# Fri3d_2020_Time_Blaster_00.net
KiCad netlist of a schematic drawn in Altium Designer
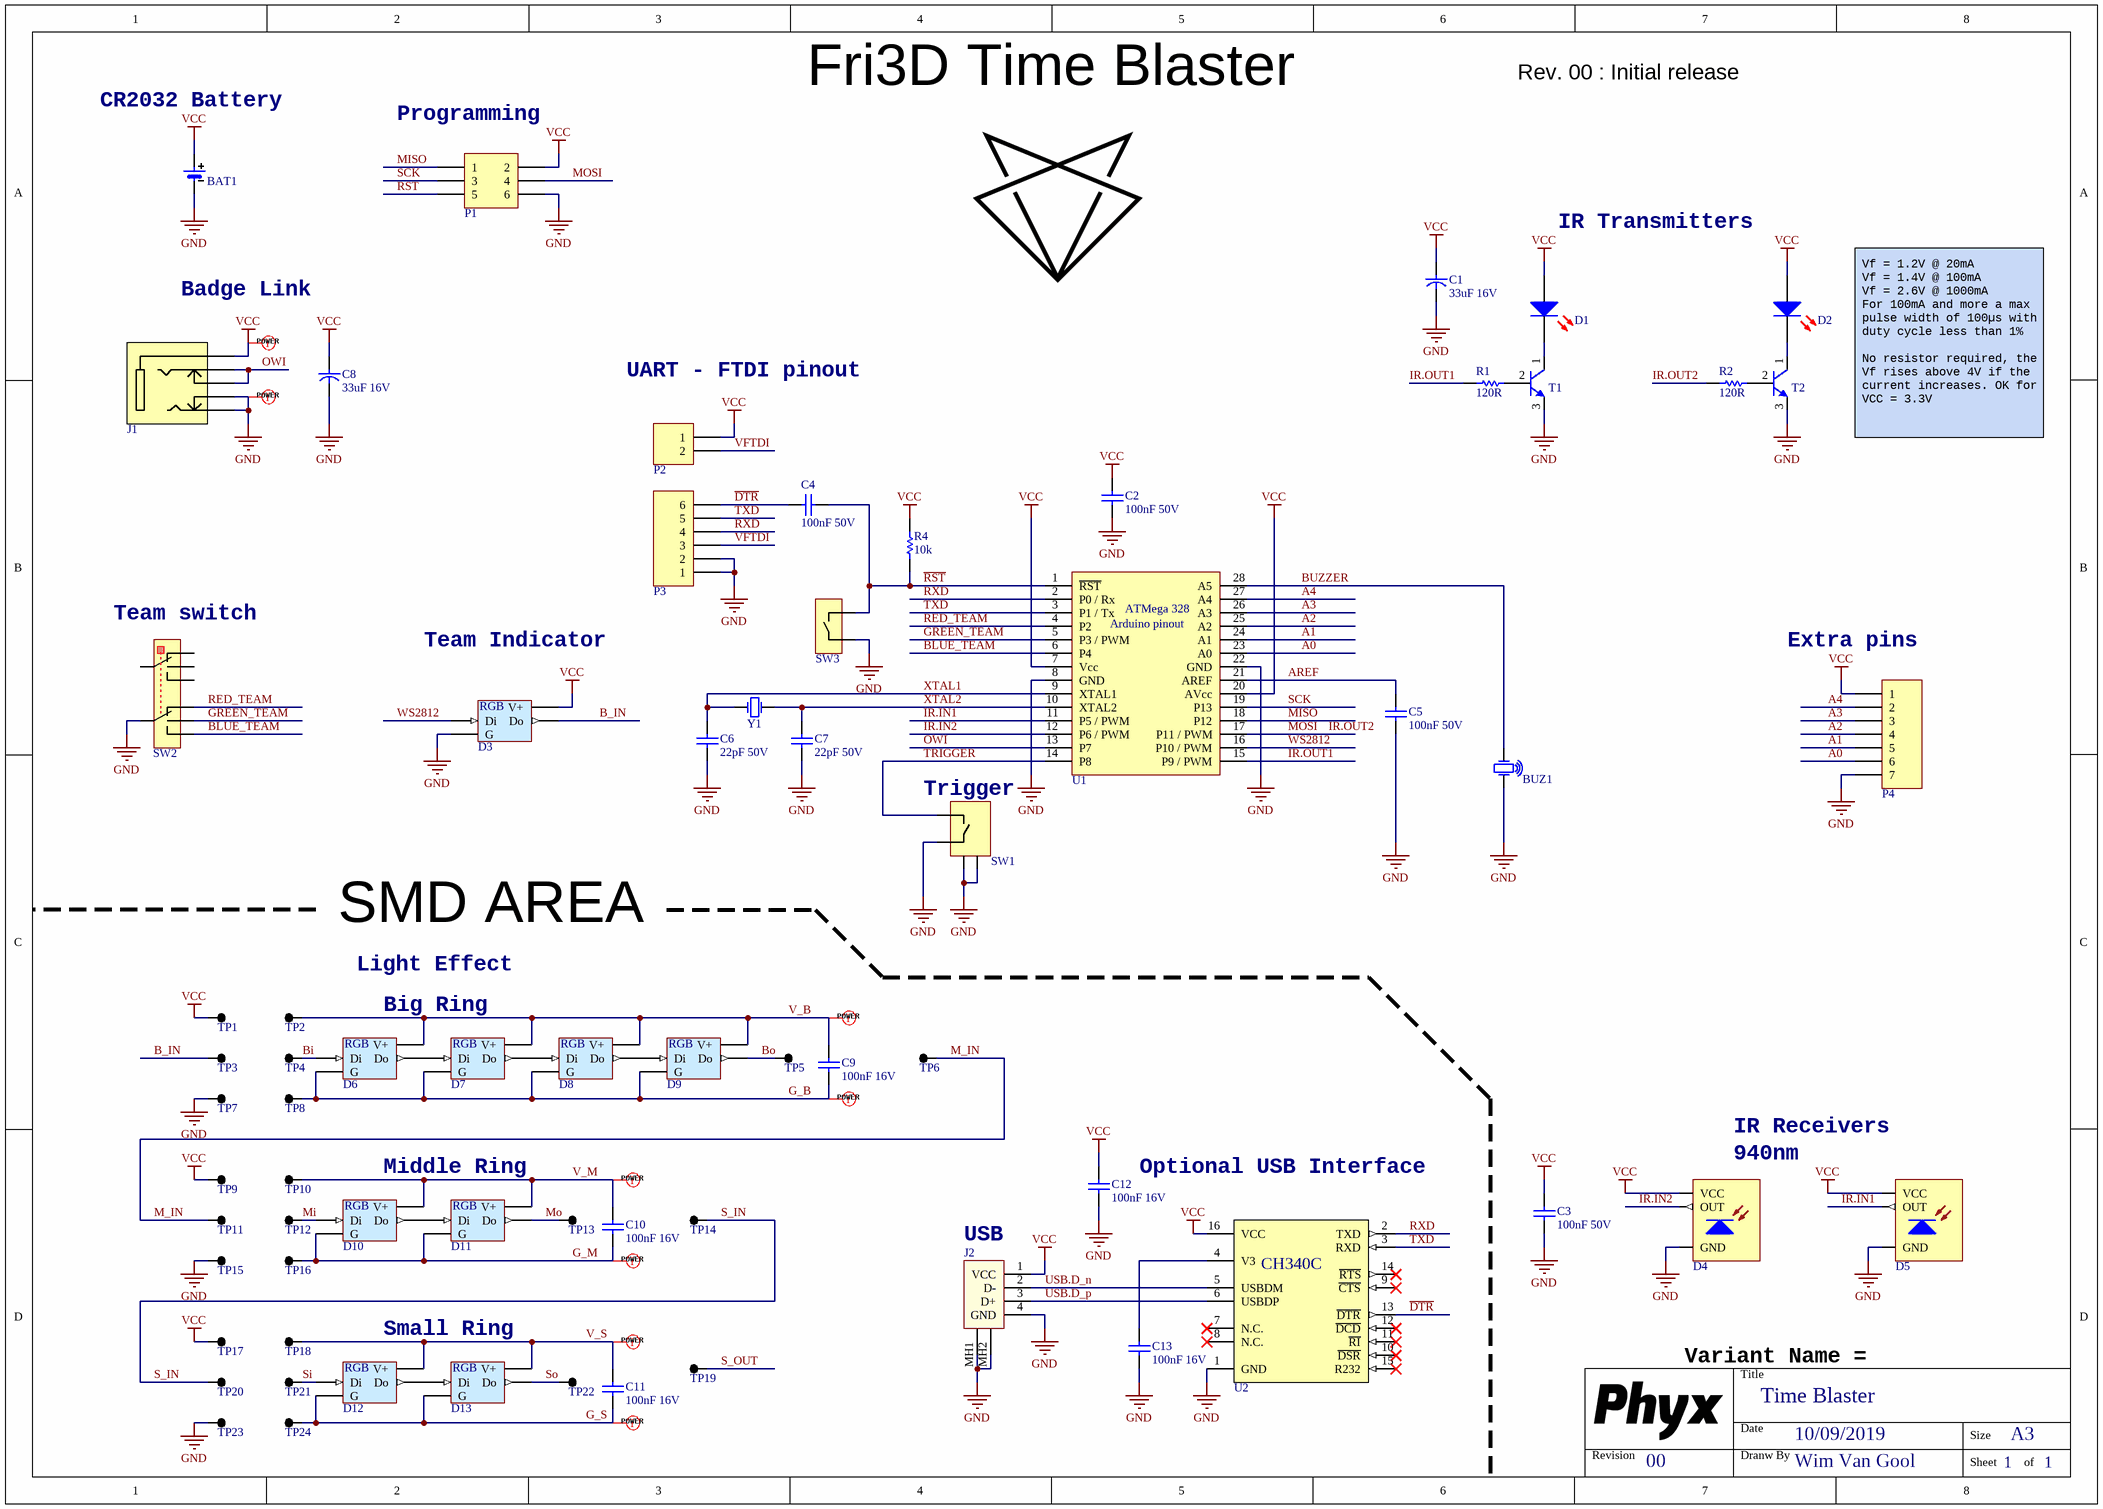
[diagram p0: Fri3d_2020_Time_Blaster_00.SchDoc]

(export (version "E")
  (design (tool "Eeschema 10.0.6"))
  (components
    (comp (ref "BAT1")
      (value "CR2032 Battery Holder")
      (footprint "BAT_CR2032_China")
      (description "=Description")
      (libsource (lib "Phyx_Components") (part "BAT_2"))
    )
    (comp (ref "BUZ1")
      (value "14x14x7mm Piezo Buzzer Transducer 80dB")
      (footprint "CUI_CEP-1162")
      (description "Crystal Oscillator")
      (libsource (lib "Phyx_Components") (part "Buzzer"))
    )
    (comp (ref "C1")
      (value "33uF 16V")
      (footprint "C_4x7_1.5mm")
      (description "Capacitor electrolyt")
      (fields (field (name "Comment") "CAP_POL"))
      (libsource (lib "Phyx_Components") (part "CAP_POL"))
    )
    (comp (ref "C2")
      (value "100nF 50V")
      (footprint "C_5.08mm")
      (description "Capacitor Ceramic")
      (fields (field (name "Comment") "CAP_CERAMIC"))
      (libsource (lib "Phyx_Components") (part "CAP_CERAMIC"))
    )
    (comp (ref "C3")
      (value "100nF 50V")
      (footprint "C_5.08mm")
      (description "Capacitor Ceramic")
      (fields (field (name "Comment") "CAP_CERAMIC"))
      (libsource (lib "Phyx_Components") (part "CAP_CERAMIC"))
    )
    (comp (ref "C4")
      (value "100nF 50V")
      (footprint "C_5.08mm")
      (description "Capacitor Ceramic")
      (fields (field (name "Comment") "CAP_CERAMIC"))
      (libsource (lib "Phyx_Components") (part "CAP_CERAMIC"))
    )
    (comp (ref "C5")
      (value "100nF 50V")
      (footprint "C_5.08mm")
      (description "Capacitor Ceramic")
      (fields (field (name "Comment") "CAP_CERAMIC"))
      (libsource (lib "Phyx_Components") (part "CAP_CERAMIC"))
    )
    (comp (ref "C6")
      (value "22pF 50V")
      (footprint "C_5.08mm")
      (description "Capacitor Ceramic")
      (fields (field (name "Comment") "CAP_CERAMIC"))
      (libsource (lib "Phyx_Components") (part "CAP_CERAMIC"))
    )
    (comp (ref "C7")
      (value "22pF 50V")
      (footprint "C_5.08mm")
      (description "Capacitor Ceramic")
      (fields (field (name "Comment") "CAP_CERAMIC"))
      (libsource (lib "Phyx_Components") (part "CAP_CERAMIC"))
    )
    (comp (ref "C8")
      (value "33uF 16V")
      (footprint "C_4x7_1.5mm")
      (description "Capacitor electrolyt")
      (fields (field (name "Comment") "CAP_POL"))
      (libsource (lib "Phyx_Components") (part "CAP_POL"))
    )
    (comp (ref "C9")
      (value "100nF 16V")
      (footprint "C0805_N")
      (description "Capacitor Ceramic")
      (fields (field (name "Comment") "CAP_CERAMIC"))
      (libsource (lib "Phyx_Components") (part "CAP_CERAMIC"))
    )
    (comp (ref "C10")
      (value "100nF 16V")
      (footprint "C0805_N")
      (description "Capacitor Ceramic")
      (fields (field (name "Comment") "CAP_CERAMIC"))
      (libsource (lib "Phyx_Components") (part "CAP_CERAMIC"))
    )
    (comp (ref "C11")
      (value "100nF 16V")
      (footprint "C0805_N")
      (description "Capacitor Ceramic")
      (fields (field (name "Comment") "CAP_CERAMIC"))
      (libsource (lib "Phyx_Components") (part "CAP_CERAMIC"))
    )
    (comp (ref "C12")
      (value "100nF 16V")
      (footprint "C0805_N")
      (description "Capacitor Ceramic")
      (fields (field (name "Comment") "CAP_CERAMIC"))
      (libsource (lib "Phyx_Components") (part "CAP_CERAMIC"))
    )
    (comp (ref "C13")
      (value "100nF 16V")
      (footprint "C0805_N")
      (description "Capacitor Ceramic")
      (fields (field (name "Comment") "CAP_CERAMIC"))
      (libsource (lib "Phyx_Components") (part "CAP_CERAMIC"))
    )
    (comp (ref "D1")
      (value "5mm IR LED, 940nm, 100mA, 1.35V, 25Deg")
      (footprint "LED_5MM_RD")
      (description "=Description")
      (libsource (lib "Phyx_Components") (part "LED_RED"))
    )
    (comp (ref "D2")
      (value "5mm IR LED, 940nm, 100mA, 1.35V, 25Deg")
      (footprint "LED_5MM_RD")
      (description "=Description")
      (libsource (lib "Phyx_Components") (part "LED_RED"))
    )
    (comp (ref "D3")
      (value "WS2812 based digital RGB LED 5mm")
      (footprint "LED_5mm_RGB")
      (description "=Description")
      (libsource (lib "Phyx_Components") (part "LED_RGB_WS2812B_5mm"))
    )
    (comp (ref "D4")
      (value "IRM-3638N3F14 Infrared Receiver 38 kHz 45° 2.7-5.5V")
      (footprint "VIS_TSOP381x_BENT")
      (description "=Description")
      (libsource (lib "Phyx_Components") (part "PHO_IR_TSOP381x"))
    )
    (comp (ref "D5")
      (value "IRM-3638N3F14 Infrared Receiver 38 kHz 45° 2.7-5.5V")
      (footprint "VIS_TSOP381x_BENT")
      (description "=Description")
      (libsource (lib "Phyx_Components") (part "PHO_IR_TSOP381x"))
    )
    (comp (ref "D6")
      (value "WS2812 based digital RGB LED 5050 Black package")
      (footprint "LED_5050_WS2812B_BLACK")
      (description "=Description")
      (libsource (lib "Phyx_Components") (part "LED_RGB_WS2812B_5050"))
    )
    (comp (ref "D7")
      (value "WS2812 based digital RGB LED 5050 Black package")
      (footprint "LED_5050_WS2812B_BLACK")
      (description "=Description")
      (libsource (lib "Phyx_Components") (part "LED_RGB_WS2812B_5050"))
    )
    (comp (ref "D8")
      (value "WS2812 based digital RGB LED 5050 Black package")
      (footprint "LED_5050_WS2812B_BLACK")
      (description "=Description")
      (libsource (lib "Phyx_Components") (part "LED_RGB_WS2812B_5050"))
    )
    (comp (ref "D9")
      (value "WS2812 based digital RGB LED 5050 Black package")
      (footprint "LED_5050_WS2812B_BLACK")
      (description "=Description")
      (libsource (lib "Phyx_Components") (part "LED_RGB_WS2812B_5050"))
    )
    (comp (ref "D10")
      (value "WS2812 based digital RGB LED 5050 Black package")
      (footprint "LED_5050_WS2812B_BLACK")
      (description "=Description")
      (libsource (lib "Phyx_Components") (part "LED_RGB_WS2812B_5050"))
    )
    (comp (ref "D11")
      (value "WS2812 based digital RGB LED 5050 Black package")
      (footprint "LED_5050_WS2812B_BLACK")
      (description "=Description")
      (libsource (lib "Phyx_Components") (part "LED_RGB_WS2812B_5050"))
    )
    (comp (ref "D12")
      (value "WS2812 based digital RGB LED 5050 Black package")
      (footprint "LED_5050_WS2812B_BLACK")
      (description "=Description")
      (libsource (lib "Phyx_Components") (part "LED_RGB_WS2812B_5050"))
    )
    (comp (ref "D13")
      (value "WS2812 based digital RGB LED 5050 Black package")
      (footprint "LED_5050_WS2812B_BLACK")
      (description "=Description")
      (libsource (lib "Phyx_Components") (part "LED_RGB_WS2812B_5050"))
    )
    (comp (ref "J1")
      (value "3.5mm jack, dual switch, black, 3 contacts")
      (footprint "CUI_SJ1-3525NG")
      (description "=Description")
      (libsource (lib "Phyx_Components") (part "CUI_SJ1-3525NG"))
    )
    (comp (ref "J2")
      (value "Vertical USB B 61400416121")
      (footprint "WE_61400416121")
      (libsource (lib "Phyx_Components") (part "USB_A"))
    )
    (comp (ref "P1")
      (value "Boxed Header 3X2")
      (footprint "B_HDR2X3")
      (libsource (lib "Phyx_Components") (part "Header 3X2"))
    )
    (comp (ref "P2")
      (value "Easy to solder connection")
      (footprint "SOLDER_SW_V_1MM")
      (libsource (lib "Phyx_Components") (part "Header 2"))
    )
    (comp (ref "P3")
      (value "Header 6")
      (footprint "HDR1X6")
      (libsource (lib "Phyx_Components") (part "Header 6"))
    )
    (comp (ref "P4")
      (value "Header 7")
      (footprint "HDR1X7")
      (libsource (lib "Phyx_Components") (part "Header 7"))
    )
    (comp (ref "R1")
      (value "120R")
      (footprint "RES_10mm")
      (fields (field (name "Comment") "RESISTOR"))
      (libsource (lib "Phyx_Components") (part "RESISTOR"))
    )
    (comp (ref "R2")
      (value "120R")
      (footprint "RES_10mm")
      (fields (field (name "Comment") "RESISTOR"))
      (libsource (lib "Phyx_Components") (part "RESISTOR"))
    )
    (comp (ref "R4")
      (value "10k")
      (footprint "RES_10mm")
      (fields (field (name "Comment") "RESISTOR"))
      (libsource (lib "Phyx_Components") (part "RESISTOR"))
    )
    (comp (ref "SW1")
      (value "Tact switch, RA, 3,85mm")
      (footprint "TACTSW_RA_385")
      (libsource (lib "Phyx_Components") (part "SW_TACT_RA"))
    )
    (comp (ref "SW2")
      (value "Slide switch dual pole triple throw")
      (footprint "CK_JS203011CQN")
      (libsource (lib "Phyx_Components") (part "SW_2P3T"))
    )
    (comp (ref "SW3")
      (value "Default TH TACT")
      (footprint "TACTSW")
      (libsource (lib "Phyx_Components") (part "SW_TACT"))
    )
    (comp (ref "T1")
      (value "0.2A 40V 100hfe NPN Transistor")
      (footprint "TO-92A")
      (libsource (lib "Phyx_Components") (part "NPN_EBC"))
    )
    (comp (ref "T2")
      (value "0.2A 40V 100hfe NPN Transistor")
      (footprint "TO-92A")
      (libsource (lib "Phyx_Components") (part "NPN_EBC"))
    )
    (comp (ref "TP1")
      (value "TEST_PAD")
      (footprint "TP_2x3mm")
      (libsource (lib "Phyx_Components") (part "TEST_PAD"))
    )
    (comp (ref "TP2")
      (value "TEST_PAD")
      (footprint "TP_2x3mm")
      (libsource (lib "Phyx_Components") (part "TEST_PAD"))
    )
    (comp (ref "TP3")
      (value "TEST_PAD")
      (footprint "TP_2x3mm")
      (libsource (lib "Phyx_Components") (part "TEST_PAD"))
    )
    (comp (ref "TP4")
      (value "TEST_PAD")
      (footprint "TP_2x3mm")
      (libsource (lib "Phyx_Components") (part "TEST_PAD"))
    )
    (comp (ref "TP5")
      (value "TEST_PAD")
      (footprint "TP_2x3mm")
      (libsource (lib "Phyx_Components") (part "TEST_PAD"))
    )
    (comp (ref "TP6")
      (value "TEST_PAD")
      (footprint "TP_2x3mm")
      (libsource (lib "Phyx_Components") (part "TEST_PAD"))
    )
    (comp (ref "TP7")
      (value "TEST_PAD")
      (footprint "TP_2x3mm")
      (libsource (lib "Phyx_Components") (part "TEST_PAD"))
    )
    (comp (ref "TP8")
      (value "TEST_PAD")
      (footprint "TP_2x3mm")
      (libsource (lib "Phyx_Components") (part "TEST_PAD"))
    )
    (comp (ref "TP9")
      (value "TEST_PAD")
      (footprint "TP_2x3mm")
      (libsource (lib "Phyx_Components") (part "TEST_PAD"))
    )
    (comp (ref "TP10")
      (value "TEST_PAD")
      (footprint "TP_2x3mm")
      (libsource (lib "Phyx_Components") (part "TEST_PAD"))
    )
    (comp (ref "TP11")
      (value "TEST_PAD")
      (footprint "TP_2x3mm")
      (libsource (lib "Phyx_Components") (part "TEST_PAD"))
    )
    (comp (ref "TP12")
      (value "TEST_PAD")
      (footprint "TP_2x3mm")
      (libsource (lib "Phyx_Components") (part "TEST_PAD"))
    )
    (comp (ref "TP13")
      (value "TEST_PAD")
      (footprint "TP_2x3mm")
      (libsource (lib "Phyx_Components") (part "TEST_PAD"))
    )
    (comp (ref "TP14")
      (value "TEST_PAD")
      (footprint "TP_2x3mm")
      (libsource (lib "Phyx_Components") (part "TEST_PAD"))
    )
    (comp (ref "TP15")
      (value "TEST_PAD")
      (footprint "TP_2x3mm")
      (libsource (lib "Phyx_Components") (part "TEST_PAD"))
    )
    (comp (ref "TP16")
      (value "TEST_PAD")
      (footprint "TP_2x3mm")
      (libsource (lib "Phyx_Components") (part "TEST_PAD"))
    )
    (comp (ref "TP17")
      (value "TEST_PAD")
      (footprint "TP_2x3mm")
      (libsource (lib "Phyx_Components") (part "TEST_PAD"))
    )
    (comp (ref "TP18")
      (value "TEST_PAD")
      (footprint "TP_2x3mm")
      (libsource (lib "Phyx_Components") (part "TEST_PAD"))
    )
    (comp (ref "TP19")
      (value "TEST_PAD")
      (footprint "TP_2x3mm")
      (libsource (lib "Phyx_Components") (part "TEST_PAD"))
    )
    (comp (ref "TP20")
      (value "TEST_PAD")
      (footprint "TP_2x3mm")
      (libsource (lib "Phyx_Components") (part "TEST_PAD"))
    )
    (comp (ref "TP21")
      (value "TEST_PAD")
      (footprint "TP_2x3mm")
      (libsource (lib "Phyx_Components") (part "TEST_PAD"))
    )
    (comp (ref "TP22")
      (value "TEST_PAD")
      (footprint "TP_2x3mm")
      (libsource (lib "Phyx_Components") (part "TEST_PAD"))
    )
    (comp (ref "TP23")
      (value "TEST_PAD")
      (footprint "TP_2x3mm")
      (libsource (lib "Phyx_Components") (part "TEST_PAD"))
    )
    (comp (ref "TP24")
      (value "TEST_PAD")
      (footprint "TP_2x3mm")
      (libsource (lib "Phyx_Components") (part "TEST_PAD"))
    )
    (comp (ref "U1")
      (value "8-bit MCU")
      (footprint "DIP_N_28")
      (libsource (lib "Phyx_Components") (part "ATMega328_DIP28"))
    )
    (comp (ref "U2")
      (value "USB to full UART with internal crystal")
      (footprint "SOIC_N_16")
      (description "=Description")
      (libsource (lib "Phyx_Components") (part "CH340C"))
    )
    (comp (ref "Y1")
      (value "16MHz 18pF HC49US")
      (footprint "HC49US")
      (description "Crystal Oscillator")
      (libsource (lib "Phyx_Components") (part "XTAL"))
    )
  )
  (nets
    (net (code "1") (name "/A0") (class "Default")
      (node (ref "P4") (pin "6") (pinfunction "6_6") (pintype "passive"))
      (node (ref "U1") (pin "23") (pinfunction "A0_23") (pintype "passive"))
    )
    (net (code "2") (name "/A1") (class "Default")
      (node (ref "P4") (pin "5") (pinfunction "5_5") (pintype "passive"))
      (node (ref "U1") (pin "24") (pinfunction "A1_24") (pintype "passive"))
    )
    (net (code "3") (name "/A2") (class "Default")
      (node (ref "P4") (pin "4") (pinfunction "4_4") (pintype "passive"))
      (node (ref "U1") (pin "25") (pinfunction "A2_25") (pintype "passive"))
    )
    (net (code "4") (name "/A3") (class "Default")
      (node (ref "P4") (pin "3") (pinfunction "3_3") (pintype "passive"))
      (node (ref "U1") (pin "26") (pinfunction "A3_26") (pintype "passive"))
    )
    (net (code "5") (name "/A4") (class "Default")
      (node (ref "P4") (pin "2") (pinfunction "2_2") (pintype "passive"))
      (node (ref "U1") (pin "27") (pinfunction "A4_27") (pintype "passive"))
    )
    (net (code "6") (name "/AREF") (class "Default")
      (node (ref "C5") (pin "1") (pinfunction "1_1") (pintype "passive"))
      (node (ref "U1") (pin "21") (pinfunction "AREF_21") (pintype "passive"))
    )
    (net (code "7") (name "/BLUE_TEAM") (class "Default")
      (node (ref "SW2") (pin "8") (pinfunction "8_8") (pintype "passive"))
      (node (ref "U1") (pin "6") (pinfunction "P4_6") (pintype "passive"))
    )
    (net (code "8") (name "/BUZZER") (class "Default")
      (node (ref "BUZ1") (pin "1") (pinfunction "OSC1_1") (pintype "passive"))
      (node (ref "U1") (pin "28") (pinfunction "A5_28") (pintype "passive"))
    )
    (net (code "9") (name "/B_IN") (class "Default")
      (node (ref "D3") (pin "1") (pinfunction "Do_1") (pintype "output"))
      (node (ref "TP3") (pin "1") (pinfunction "1_1") (pintype "passive"))
    )
    (net (code "10") (name "/Bi") (class "Default")
      (node (ref "D6") (pin "4") (pinfunction "Di_4") (pintype "input"))
      (node (ref "TP4") (pin "1") (pinfunction "1_1") (pintype "passive"))
    )
    (net (code "11") (name "/Bo") (class "Default")
      (node (ref "D9") (pin "2") (pinfunction "Do_2") (pintype "output"))
      (node (ref "TP5") (pin "1") (pinfunction "1_1") (pintype "passive"))
    )
    (net (code "12") (name "/GREEN_TEAM") (class "Default")
      (node (ref "SW2") (pin "6") (pinfunction "6_6") (pintype "passive"))
      (node (ref "U1") (pin "5") (pinfunction "P3_/_PWM_5") (pintype "passive"))
    )
    (net (code "13") (name "/G_B") (class "Default")
      (node (ref "C9") (pin "2") (pinfunction "2_2") (pintype "passive"))
      (node (ref "D6") (pin "3") (pinfunction "G_3") (pintype "power_in"))
      (node (ref "D7") (pin "3") (pinfunction "G_3") (pintype "power_in"))
      (node (ref "D8") (pin "3") (pinfunction "G_3") (pintype "power_in"))
      (node (ref "D9") (pin "3") (pinfunction "G_3") (pintype "power_in"))
      (node (ref "TP8") (pin "1") (pinfunction "1_1") (pintype "passive"))
    )
    (net (code "14") (name "/G_M") (class "Default")
      (node (ref "C10") (pin "2") (pinfunction "2_2") (pintype "passive"))
      (node (ref "D10") (pin "3") (pinfunction "G_3") (pintype "power_in"))
      (node (ref "D11") (pin "3") (pinfunction "G_3") (pintype "power_in"))
      (node (ref "TP16") (pin "1") (pinfunction "1_1") (pintype "passive"))
    )
    (net (code "15") (name "/G_S") (class "Default")
      (node (ref "C11") (pin "2") (pinfunction "2_2") (pintype "passive"))
      (node (ref "D12") (pin "3") (pinfunction "G_3") (pintype "power_in"))
      (node (ref "D13") (pin "3") (pinfunction "G_3") (pintype "power_in"))
      (node (ref "TP24") (pin "1") (pinfunction "1_1") (pintype "passive"))
    )
    (net (code "16") (name "/IR.IN1") (class "Default")
      (node (ref "D5") (pin "1") (pinfunction "OUT_1") (pintype "output"))
      (node (ref "U1") (pin "11") (pinfunction "P5_/_PWM_11") (pintype "passive"))
    )
    (net (code "17") (name "/IR.IN2") (class "Default")
      (node (ref "D4") (pin "1") (pinfunction "OUT_1") (pintype "output"))
      (node (ref "U1") (pin "12") (pinfunction "P6_/_PWM_12") (pintype "passive"))
    )
    (net (code "18") (name "/IR.OUT1") (class "Default")
      (node (ref "R1") (pin "2") (pinfunction "2_2") (pintype "passive"))
      (node (ref "U1") (pin "15") (pinfunction "P9_/_PWM_15") (pintype "passive"))
    )
    (net (code "19") (name "/IR.OUT2") (class "Default")
      (node (ref "P1") (pin "4") (pinfunction "4_4") (pintype "passive"))
      (node (ref "R2") (pin "2") (pinfunction "2_2") (pintype "passive"))
      (node (ref "U1") (pin "17") (pinfunction "P11_/_PWM_17") (pintype "passive"))
    )
    (net (code "20") (name "/MISO") (class "Default")
      (node (ref "P1") (pin "1") (pinfunction "1_1") (pintype "passive"))
      (node (ref "U1") (pin "18") (pinfunction "P12_18") (pintype "passive"))
    )
    (net (code "21") (name "/M_IN") (class "Default")
      (node (ref "TP11") (pin "1") (pinfunction "1_1") (pintype "passive"))
      (node (ref "TP6") (pin "1") (pinfunction "1_1") (pintype "passive"))
    )
    (net (code "22") (name "/Mi") (class "Default")
      (node (ref "D10") (pin "4") (pinfunction "Di_4") (pintype "input"))
      (node (ref "TP12") (pin "1") (pinfunction "1_1") (pintype "passive"))
    )
    (net (code "23") (name "/Mo") (class "Default")
      (node (ref "D11") (pin "2") (pinfunction "Do_2") (pintype "output"))
      (node (ref "TP13") (pin "1") (pinfunction "1_1") (pintype "passive"))
    )
    (net (code "24") (name "/OWI") (class "Default")
      (node (ref "J1") (pin "3") (pinfunction "Ring_3") (pintype "passive"))
      (node (ref "J1") (pin "5") (pinfunction "5_5") (pintype "passive"))
      (node (ref "U1") (pin "13") (pinfunction "P7_13") (pintype "passive"))
    )
    (net (code "25") (name "/RED_TEAM") (class "Default")
      (node (ref "SW2") (pin "5") (pinfunction "5_5") (pintype "passive"))
      (node (ref "U1") (pin "4") (pinfunction "P2_4") (pintype "passive"))
    )
    (net (code "26") (name "/RXD") (class "Default")
      (node (ref "P3") (pin "4") (pinfunction "4_4") (pintype "passive"))
      (node (ref "U1") (pin "2") (pinfunction "P0_/_Rx_2") (pintype "passive"))
      (node (ref "U2") (pin "2") (pinfunction "TXD_2") (pintype "output"))
    )
    (net (code "27") (name "/SCK") (class "Default")
      (node (ref "P1") (pin "3") (pinfunction "3_3") (pintype "passive"))
      (node (ref "U1") (pin "19") (pinfunction "P13_19") (pintype "passive"))
    )
    (net (code "28") (name "/S_IN") (class "Default")
      (node (ref "TP14") (pin "1") (pinfunction "1_1") (pintype "passive"))
      (node (ref "TP20") (pin "1") (pinfunction "1_1") (pintype "passive"))
    )
    (net (code "29") (name "/S_OUT") (class "Default")
      (node (ref "TP19") (pin "1") (pinfunction "1_1") (pintype "passive"))
    )
    (net (code "30") (name "/Si") (class "Default")
      (node (ref "D12") (pin "4") (pinfunction "Di_4") (pintype "input"))
      (node (ref "TP21") (pin "1") (pinfunction "1_1") (pintype "passive"))
    )
    (net (code "31") (name "/So") (class "Default")
      (node (ref "D13") (pin "2") (pinfunction "Do_2") (pintype "output"))
      (node (ref "TP22") (pin "1") (pinfunction "1_1") (pintype "passive"))
    )
    (net (code "32") (name "/TRIGGER") (class "Default")
      (node (ref "SW1") (pin "1") (pinfunction "1_1") (pintype "passive"))
      (node (ref "U1") (pin "14") (pinfunction "P8_14") (pintype "passive"))
    )
    (net (code "33") (name "/TXD") (class "Default")
      (node (ref "P3") (pin "5") (pinfunction "5_5") (pintype "passive"))
      (node (ref "U1") (pin "3") (pinfunction "P1_/_Tx_3") (pintype "passive"))
      (node (ref "U2") (pin "3") (pinfunction "RXD_3") (pintype "input"))
    )
    (net (code "34") (name "/USB.D_n") (class "Default")
      (node (ref "J2") (pin "2") (pinfunction "D-_2") (pintype "passive"))
      (node (ref "U2") (pin "5") (pinfunction "USBDM_5") (pintype "passive"))
    )
    (net (code "35") (name "/USB.D_p") (class "Default")
      (node (ref "J2") (pin "3") (pinfunction "D+_3") (pintype "passive"))
      (node (ref "U2") (pin "6") (pinfunction "USBDP_6") (pintype "passive"))
    )
    (net (code "36") (name "/VFTDI") (class "Default")
      (node (ref "P2") (pin "2") (pinfunction "2_2") (pintype "passive"))
      (node (ref "P3") (pin "3") (pinfunction "3_3") (pintype "passive"))
    )
    (net (code "37") (name "/V_B") (class "Default")
      (node (ref "C9") (pin "1") (pinfunction "1_1") (pintype "passive"))
      (node (ref "D6") (pin "1") (pinfunction "V+_1") (pintype "power_in"))
      (node (ref "D7") (pin "1") (pinfunction "V+_1") (pintype "power_in"))
      (node (ref "D8") (pin "1") (pinfunction "V+_1") (pintype "power_in"))
      (node (ref "D9") (pin "1") (pinfunction "V+_1") (pintype "power_in"))
      (node (ref "TP2") (pin "1") (pinfunction "1_1") (pintype "passive"))
    )
    (net (code "38") (name "/V_M") (class "Default")
      (node (ref "C10") (pin "1") (pinfunction "1_1") (pintype "passive"))
      (node (ref "D10") (pin "1") (pinfunction "V+_1") (pintype "power_in"))
      (node (ref "D11") (pin "1") (pinfunction "V+_1") (pintype "power_in"))
      (node (ref "TP10") (pin "1") (pinfunction "1_1") (pintype "passive"))
    )
    (net (code "39") (name "/V_S") (class "Default")
      (node (ref "C11") (pin "1") (pinfunction "1_1") (pintype "passive"))
      (node (ref "D12") (pin "1") (pinfunction "V+_1") (pintype "power_in"))
      (node (ref "D13") (pin "1") (pinfunction "V+_1") (pintype "power_in"))
      (node (ref "TP18") (pin "1") (pinfunction "1_1") (pintype "passive"))
    )
    (net (code "40") (name "/WS2812") (class "Default")
      (node (ref "D3") (pin "4") (pinfunction "Di_4") (pintype "input"))
      (node (ref "U1") (pin "16") (pinfunction "P10_/_PWM_16") (pintype "passive"))
    )
    (net (code "41") (name "/XTAL1") (class "Default")
      (node (ref "C6") (pin "1") (pinfunction "1_1") (pintype "passive"))
      (node (ref "U1") (pin "9") (pinfunction "XTAL1_9") (pintype "passive"))
      (node (ref "Y1") (pin "1") (pinfunction "OSC1_1") (pintype "passive"))
    )
    (net (code "42") (name "/XTAL2") (class "Default")
      (node (ref "C7") (pin "1") (pinfunction "1_1") (pintype "passive"))
      (node (ref "U1") (pin "10") (pinfunction "XTAL2_10") (pintype "passive"))
      (node (ref "Y1") (pin "2") (pinfunction "OSC2_2") (pintype "passive"))
    )
    (net (code "43") (name "/~{DTR}") (class "Default")
      (node (ref "C4") (pin "2") (pinfunction "2_2") (pintype "passive"))
      (node (ref "P3") (pin "6") (pinfunction "6_6") (pintype "passive"))
      (node (ref "U2") (pin "13") (pinfunction "~{DTR}_13") (pintype "output"))
    )
    (net (code "44") (name "/~{RST}") (class "Default")
      (node (ref "C4") (pin "1") (pinfunction "1_1") (pintype "passive"))
      (node (ref "P1") (pin "5") (pinfunction "5_5") (pintype "passive"))
      (node (ref "R4") (pin "2") (pinfunction "2_2") (pintype "passive"))
      (node (ref "SW3") (pin "1") (pinfunction "1_1") (pintype "passive"))
      (node (ref "U1") (pin "1") (pinfunction "~{RST}_1") (pintype "passive"))
    )
    (net (code "45") (name "GND") (class "Default")
      (node (ref "BAT1") (pin "2") (pinfunction "2_2") (pintype "passive"))
      (node (ref "BUZ1") (pin "2") (pinfunction "OSC2_2") (pintype "passive"))
      (node (ref "C1") (pin "2") (pinfunction "2_2") (pintype "passive"))
      (node (ref "C12") (pin "2") (pinfunction "2_2") (pintype "passive"))
      (node (ref "C13") (pin "2") (pinfunction "2_2") (pintype "passive"))
      (node (ref "C2") (pin "2") (pinfunction "2_2") (pintype "passive"))
      (node (ref "C3") (pin "2") (pinfunction "2_2") (pintype "passive"))
      (node (ref "C5") (pin "2") (pinfunction "2_2") (pintype "passive"))
      (node (ref "C6") (pin "2") (pinfunction "2_2") (pintype "passive"))
      (node (ref "C7") (pin "2") (pinfunction "2_2") (pintype "passive"))
      (node (ref "C8") (pin "2") (pinfunction "2_2") (pintype "passive"))
      (node (ref "D3") (pin "3") (pinfunction "G_3") (pintype "power_in"))
      (node (ref "D4") (pin "2") (pinfunction "GND_2") (pintype "power_in"))
      (node (ref "D5") (pin "2") (pinfunction "GND_2") (pintype "power_in"))
      (node (ref "J1") (pin "2") (pinfunction "Tip_2") (pintype "passive"))
      (node (ref "J1") (pin "4") (pinfunction "4_4") (pintype "passive"))
      (node (ref "J2") (pin "4") (pinfunction "GND_4") (pintype "passive"))
      (node (ref "J2") (pin "MH1") (pinfunction "Tab_MH1") (pintype "passive"))
      (node (ref "J2") (pin "MH2") (pinfunction "Tab_MH2") (pintype "passive"))
      (node (ref "P1") (pin "6") (pinfunction "6_6") (pintype "passive"))
      (node (ref "P3") (pin "1") (pinfunction "1_1") (pintype "passive"))
      (node (ref "P3") (pin "2") (pinfunction "2_2") (pintype "passive"))
      (node (ref "P4") (pin "7") (pinfunction "7_7") (pintype "passive"))
      (node (ref "SW1") (pin "2") (pinfunction "2_2") (pintype "passive"))
      (node (ref "SW1") (pin "MH1") (pinfunction "MH1_MH1") (pintype "passive"))
      (node (ref "SW1") (pin "MH2") (pinfunction "MH2_MH2") (pintype "passive"))
      (node (ref "SW2") (pin "7") (pinfunction "7_7") (pintype "passive"))
      (node (ref "SW3") (pin "2") (pinfunction "2_2") (pintype "passive"))
      (node (ref "T1") (pin "3") (pinfunction "E_3") (pintype "passive"))
      (node (ref "T2") (pin "3") (pinfunction "E_3") (pintype "passive"))
      (node (ref "TP15") (pin "1") (pinfunction "1_1") (pintype "passive"))
      (node (ref "TP23") (pin "1") (pinfunction "1_1") (pintype "passive"))
      (node (ref "TP7") (pin "1") (pinfunction "1_1") (pintype "passive"))
      (node (ref "U1") (pin "22") (pinfunction "GND_22") (pintype "power_in"))
      (node (ref "U1") (pin "8") (pinfunction "GND_8") (pintype "power_in"))
      (node (ref "U2") (pin "1") (pinfunction "GND_1") (pintype "power_in"))
    )
    (net (code "46") (name "Net-(D1-K)") (class "Default")
      (node (ref "D1") (pin "2") (pinfunction "K_2") (pintype "passive"))
      (node (ref "T1") (pin "1") (pinfunction "C_1") (pintype "passive"))
    )
    (net (code "47") (name "Net-(D2-K)") (class "Default")
      (node (ref "D2") (pin "2") (pinfunction "K_2") (pintype "passive"))
      (node (ref "T2") (pin "1") (pinfunction "C_1") (pintype "passive"))
    )
    (net (code "48") (name "Net-(D6-Do)") (class "Default")
      (node (ref "D6") (pin "2") (pinfunction "Do_2") (pintype "output"))
      (node (ref "D7") (pin "4") (pinfunction "Di_4") (pintype "input"))
    )
    (net (code "49") (name "Net-(D7-Do)") (class "Default")
      (node (ref "D7") (pin "2") (pinfunction "Do_2") (pintype "output"))
      (node (ref "D8") (pin "4") (pinfunction "Di_4") (pintype "input"))
    )
    (net (code "50") (name "Net-(D8-Do)") (class "Default")
      (node (ref "D8") (pin "2") (pinfunction "Do_2") (pintype "output"))
      (node (ref "D9") (pin "4") (pinfunction "Di_4") (pintype "input"))
    )
    (net (code "51") (name "Net-(D10-Do)") (class "Default")
      (node (ref "D10") (pin "2") (pinfunction "Do_2") (pintype "output"))
      (node (ref "D11") (pin "4") (pinfunction "Di_4") (pintype "input"))
    )
    (net (code "52") (name "Net-(D12-Do)") (class "Default")
      (node (ref "D12") (pin "2") (pinfunction "Do_2") (pintype "output"))
      (node (ref "D13") (pin "4") (pinfunction "Di_4") (pintype "input"))
    )
    (net (code "53") (name "Net-(T1-B)") (class "Default")
      (node (ref "R1") (pin "1") (pinfunction "1_1") (pintype "passive"))
      (node (ref "T1") (pin "2") (pinfunction "B_2") (pintype "passive"))
    )
    (net (code "54") (name "Net-(T2-B)") (class "Default")
      (node (ref "R2") (pin "1") (pinfunction "1_1") (pintype "passive"))
      (node (ref "T2") (pin "2") (pinfunction "B_2") (pintype "passive"))
    )
    (net (code "55") (name "Net-(U2-V3)") (class "Default")
      (node (ref "C13") (pin "1") (pinfunction "1_1") (pintype "passive"))
      (node (ref "U2") (pin "4") (pinfunction "V3_4") (pintype "power_in"))
    )
    (net (code "56") (name "VCC") (class "Default")
      (node (ref "BAT1") (pin "1") (pinfunction "1_1") (pintype "passive"))
      (node (ref "C1") (pin "1") (pinfunction "1_1") (pintype "passive"))
      (node (ref "C12") (pin "1") (pinfunction "1_1") (pintype "passive"))
      (node (ref "C2") (pin "1") (pinfunction "1_1") (pintype "passive"))
      (node (ref "C3") (pin "1") (pinfunction "1_1") (pintype "passive"))
      (node (ref "C8") (pin "1") (pinfunction "1_1") (pintype "passive"))
      (node (ref "D1") (pin "1") (pinfunction "A_1") (pintype "passive"))
      (node (ref "D2") (pin "1") (pinfunction "A_1") (pintype "passive"))
      (node (ref "D3") (pin "2") (pinfunction "V+_2") (pintype "power_in"))
      (node (ref "D4") (pin "3") (pinfunction "VCC_3") (pintype "power_in"))
      (node (ref "D5") (pin "3") (pinfunction "VCC_3") (pintype "power_in"))
      (node (ref "J1") (pin "1") (pinfunction "Sleeve_1") (pintype "passive"))
      (node (ref "J2") (pin "1") (pinfunction "VCC_1") (pintype "passive"))
      (node (ref "P1") (pin "2") (pinfunction "2_2") (pintype "passive"))
      (node (ref "P2") (pin "1") (pinfunction "1_1") (pintype "passive"))
      (node (ref "P4") (pin "1") (pinfunction "1_1") (pintype "passive"))
      (node (ref "R4") (pin "1") (pinfunction "1_1") (pintype "passive"))
      (node (ref "TP1") (pin "1") (pinfunction "1_1") (pintype "passive"))
      (node (ref "TP17") (pin "1") (pinfunction "1_1") (pintype "passive"))
      (node (ref "TP9") (pin "1") (pinfunction "1_1") (pintype "passive"))
      (node (ref "U1") (pin "20") (pinfunction "AVcc_20") (pintype "power_in"))
      (node (ref "U1") (pin "7") (pinfunction "Vcc_7") (pintype "power_in"))
      (node (ref "U2") (pin "16") (pinfunction "VCC_16") (pintype "power_in"))
    )
    (net (code "57") (name "unconnected-(SW2-Pad1)") (class "Default")
      (node (ref "SW2") (pin "1") (pinfunction "1_1") (pintype "passive"))
    )
    (net (code "58") (name "unconnected-(SW2-Pad2)") (class "Default")
      (node (ref "SW2") (pin "2") (pinfunction "2_2") (pintype "passive"))
    )
    (net (code "59") (name "unconnected-(SW2-Pad3)") (class "Default")
      (node (ref "SW2") (pin "3") (pinfunction "3_3") (pintype "passive"))
    )
    (net (code "60") (name "unconnected-(SW2-Pad4)") (class "Default")
      (node (ref "SW2") (pin "4") (pinfunction "4_4") (pintype "passive"))
    )
    (net (code "61") (name "unconnected-(U2-N.C.-Pad7)") (class "Default")
      (node (ref "U2") (pin "7") (pinfunction "N.C._7") (pintype "passive+no_connect"))
    )
    (net (code "62") (name "unconnected-(U2-N.C.-Pad8)") (class "Default")
      (node (ref "U2") (pin "8") (pinfunction "N.C._8") (pintype "passive+no_connect"))
    )
    (net (code "63") (name "unconnected-(U2-R232-Pad15)") (class "Default")
      (node (ref "U2") (pin "15") (pinfunction "R232_15") (pintype "input+no_connect"))
    )
    (net (code "64") (name "unconnected-(U2-~{CTS}-Pad9)") (class "Default")
      (node (ref "U2") (pin "9") (pinfunction "~{CTS}_9") (pintype "input+no_connect"))
    )
    (net (code "65") (name "unconnected-(U2-~{DCD}-Pad12)") (class "Default")
      (node (ref "U2") (pin "12") (pinfunction "~{DCD}_12") (pintype "input+no_connect"))
    )
    (net (code "66") (name "unconnected-(U2-~{DSR}-Pad10)") (class "Default")
      (node (ref "U2") (pin "10") (pinfunction "~{DSR}_10") (pintype "input+no_connect"))
    )
    (net (code "67") (name "unconnected-(U2-~{RI}-Pad11)") (class "Default")
      (node (ref "U2") (pin "11") (pinfunction "~{RI}_11") (pintype "input+no_connect"))
    )
    (net (code "68") (name "unconnected-(U2-~{RTS}-Pad14)") (class "Default")
      (node (ref "U2") (pin "14") (pinfunction "~{RTS}_14") (pintype "output+no_connect"))
    )
  )
)
